# store-row-select.net
KiCad netlist of a schematic drawn in EAGLE
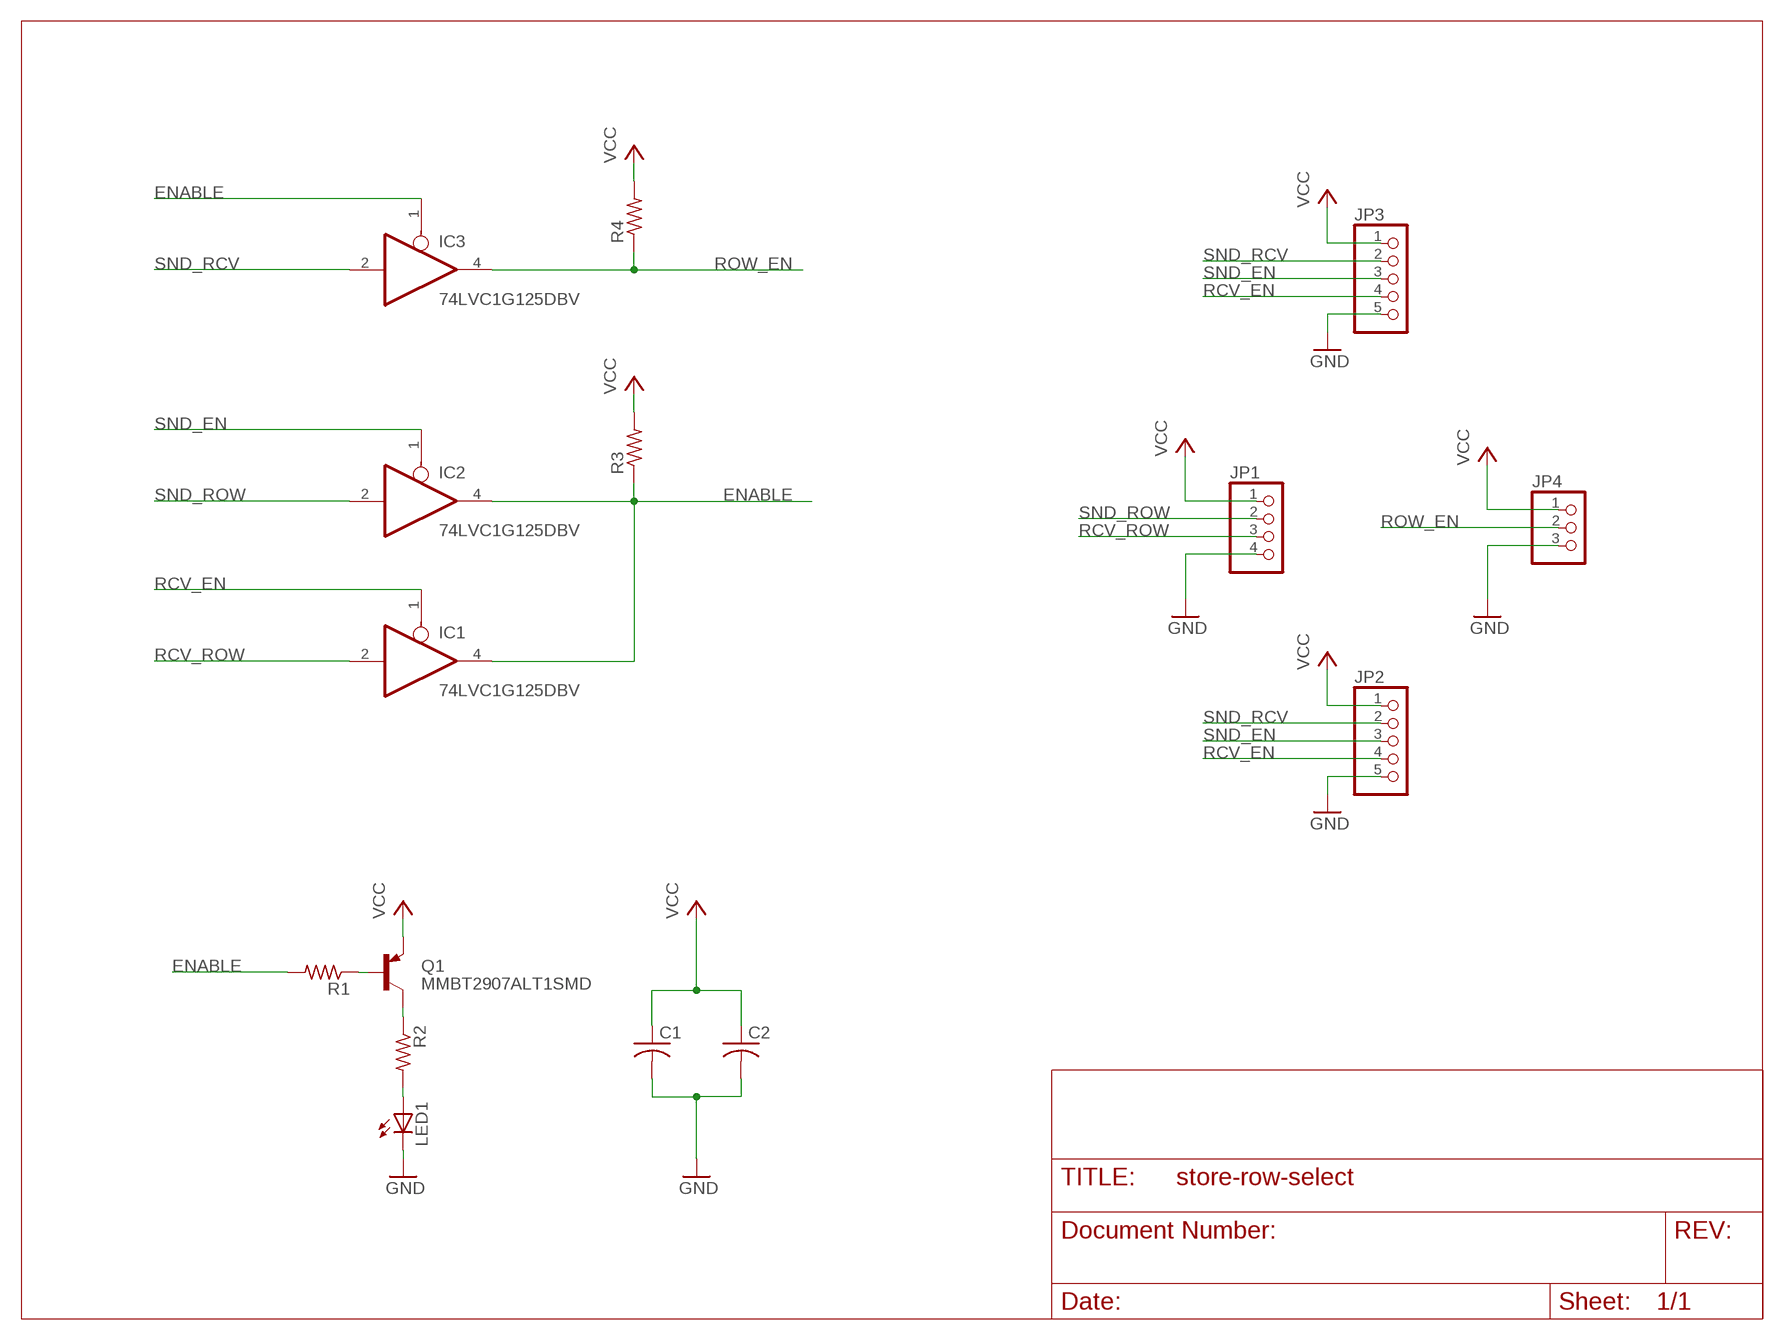
[diagram p0: schematic, sheet 1]

(export (version "E")
  (design (tool "Eeschema 10.0.6"))
  (components
    (comp (ref "C1")
      (value "C-USC0805")
      (footprint "eagle-import:C0805")
      (libsource (lib "eagle-import") (part "C-USC0805"))
    )
    (comp (ref "C2")
      (value "C-USC0805")
      (footprint "eagle-import:C0805")
      (libsource (lib "eagle-import") (part "C-USC0805"))
    )
    (comp (ref "IC1")
      (value "74LVC1G125DBV")
      (footprint "eagle-import:SOT23-5")
      (libsource (lib "eagle-import") (part "741G125DBVLVC"))
    )
    (comp (ref "IC2")
      (value "74LVC1G125DBV")
      (footprint "eagle-import:SOT23-5")
      (libsource (lib "eagle-import") (part "741G125DBVLVC"))
    )
    (comp (ref "IC3")
      (value "74LVC1G125DBV")
      (footprint "eagle-import:SOT23-5")
      (libsource (lib "eagle-import") (part "741G125DBVLVC"))
    )
    (comp (ref "JP1")
      (value "PINHD-1X4")
      (footprint "eagle-import:1X04")
      (libsource (lib "eagle-import") (part "PINHD-1X4"))
    )
    (comp (ref "JP2")
      (value "PINHD-1X5")
      (footprint "eagle-import:1X05")
      (libsource (lib "eagle-import") (part "PINHD-1X5"))
    )
    (comp (ref "JP3")
      (value "PINHD-1X5")
      (footprint "eagle-import:1X05")
      (libsource (lib "eagle-import") (part "PINHD-1X5"))
    )
    (comp (ref "JP4")
      (value "PINHD-1X3")
      (footprint "eagle-import:1X03")
      (libsource (lib "eagle-import") (part "PINHD-1X3"))
    )
    (comp (ref "LED1")
      (value "LEDCHIP-LED0805")
      (footprint "eagle-import:CHIP-LED0805")
      (libsource (lib "eagle-import") (part "LEDCHIP-LED0805"))
    )
    (comp (ref "Q1")
      (value "MMBT2907ALT1SMD")
      (footprint "eagle-import:SOT23-BEC")
      (libsource (lib "eagle-import") (part "MMBT2907SMDALT1"))
    )
    (comp (ref "R1")
      (value "R-US_R0805")
      (footprint "eagle-import:R0805")
      (libsource (lib "eagle-import") (part "R-US_R0805"))
    )
    (comp (ref "R2")
      (value "R-US_R0805")
      (footprint "eagle-import:R0805")
      (libsource (lib "eagle-import") (part "R-US_R0805"))
    )
    (comp (ref "R3")
      (value "R-US_R0805")
      (footprint "eagle-import:R0805")
      (libsource (lib "eagle-import") (part "R-US_R0805"))
    )
    (comp (ref "R4")
      (value "R-US_R0805")
      (footprint "eagle-import:R0805")
      (libsource (lib "eagle-import") (part "R-US_R0805"))
    )
  )
  (nets
    (net (code "1") (name "/ENABLE") (class "Default")
      (node (ref "IC1") (pin "4") (pinfunction "O_4") (pintype "tri_state"))
      (node (ref "IC2") (pin "4") (pinfunction "O_4") (pintype "tri_state"))
      (node (ref "IC3") (pin "1") (pinfunction "OE_1") (pintype "input"))
      (node (ref "R1") (pin "2") (pinfunction "2_2") (pintype "passive"))
      (node (ref "R3") (pin "1") (pinfunction "1_1") (pintype "passive"))
    )
    (net (code "2") (name "/RCV_EN") (class "Default")
      (node (ref "IC1") (pin "1") (pinfunction "OE_1") (pintype "input"))
      (node (ref "JP2") (pin "4") (pinfunction "4_4") (pintype "passive"))
      (node (ref "JP3") (pin "4") (pinfunction "4_4") (pintype "passive"))
    )
    (net (code "3") (name "/RCV_ROW") (class "Default")
      (node (ref "IC1") (pin "2") (pinfunction "I_2") (pintype "input"))
      (node (ref "JP1") (pin "3") (pinfunction "3_3") (pintype "passive"))
    )
    (net (code "4") (name "/ROW_EN") (class "Default")
      (node (ref "IC3") (pin "4") (pinfunction "O_4") (pintype "tri_state"))
      (node (ref "JP4") (pin "2") (pinfunction "2_2") (pintype "passive"))
      (node (ref "R4") (pin "1") (pinfunction "1_1") (pintype "passive"))
    )
    (net (code "5") (name "/SND_EN") (class "Default")
      (node (ref "IC2") (pin "1") (pinfunction "OE_1") (pintype "input"))
      (node (ref "JP2") (pin "3") (pinfunction "3_3") (pintype "passive"))
      (node (ref "JP3") (pin "3") (pinfunction "3_3") (pintype "passive"))
    )
    (net (code "6") (name "/SND_RCV") (class "Default")
      (node (ref "IC3") (pin "2") (pinfunction "I_2") (pintype "input"))
      (node (ref "JP2") (pin "2") (pinfunction "2_2") (pintype "passive"))
      (node (ref "JP3") (pin "2") (pinfunction "2_2") (pintype "passive"))
    )
    (net (code "7") (name "/SND_ROW") (class "Default")
      (node (ref "IC2") (pin "2") (pinfunction "I_2") (pintype "input"))
      (node (ref "JP1") (pin "2") (pinfunction "2_2") (pintype "passive"))
    )
    (net (code "8") (name "GND") (class "Default")
      (node (ref "C1") (pin "2") (pinfunction "2_2") (pintype "passive"))
      (node (ref "C2") (pin "2") (pinfunction "2_2") (pintype "passive"))
      (node (ref "JP1") (pin "4") (pinfunction "4_4") (pintype "passive"))
      (node (ref "JP2") (pin "5") (pinfunction "5_5") (pintype "passive"))
      (node (ref "JP3") (pin "5") (pinfunction "5_5") (pintype "passive"))
      (node (ref "JP4") (pin "3") (pinfunction "3_3") (pintype "passive"))
      (node (ref "LED1") (pin "C") (pinfunction "C_C") (pintype "passive"))
    )
    (net (code "9") (name "Net-(LED1-PadA)") (class "Default")
      (node (ref "LED1") (pin "A") (pinfunction "A_A") (pintype "passive"))
      (node (ref "R2") (pin "2") (pinfunction "2_2") (pintype "passive"))
    )
    (net (code "10") (name "Net-(Q1-PadB)") (class "Default")
      (node (ref "Q1") (pin "B") (pinfunction "B_B") (pintype "passive"))
      (node (ref "R1") (pin "1") (pinfunction "1_1") (pintype "passive"))
    )
    (net (code "11") (name "Net-(Q1-PadC)") (class "Default")
      (node (ref "Q1") (pin "C") (pinfunction "C_C") (pintype "passive"))
      (node (ref "R2") (pin "1") (pinfunction "1_1") (pintype "passive"))
    )
    (net (code "12") (name "VCC") (class "Default")
      (node (ref "C1") (pin "1") (pinfunction "1_1") (pintype "passive"))
      (node (ref "C2") (pin "1") (pinfunction "1_1") (pintype "passive"))
      (node (ref "JP1") (pin "1") (pinfunction "1_1") (pintype "passive"))
      (node (ref "JP2") (pin "1") (pinfunction "1_1") (pintype "passive"))
      (node (ref "JP3") (pin "1") (pinfunction "1_1") (pintype "passive"))
      (node (ref "JP4") (pin "1") (pinfunction "1_1") (pintype "passive"))
      (node (ref "Q1") (pin "E") (pinfunction "E_E") (pintype "passive"))
      (node (ref "R3") (pin "2") (pinfunction "2_2") (pintype "passive"))
      (node (ref "R4") (pin "2") (pinfunction "2_2") (pintype "passive"))
    )
  )
)
